# Lion1.net
KiCad netlist of a schematic drawn in EAGLE
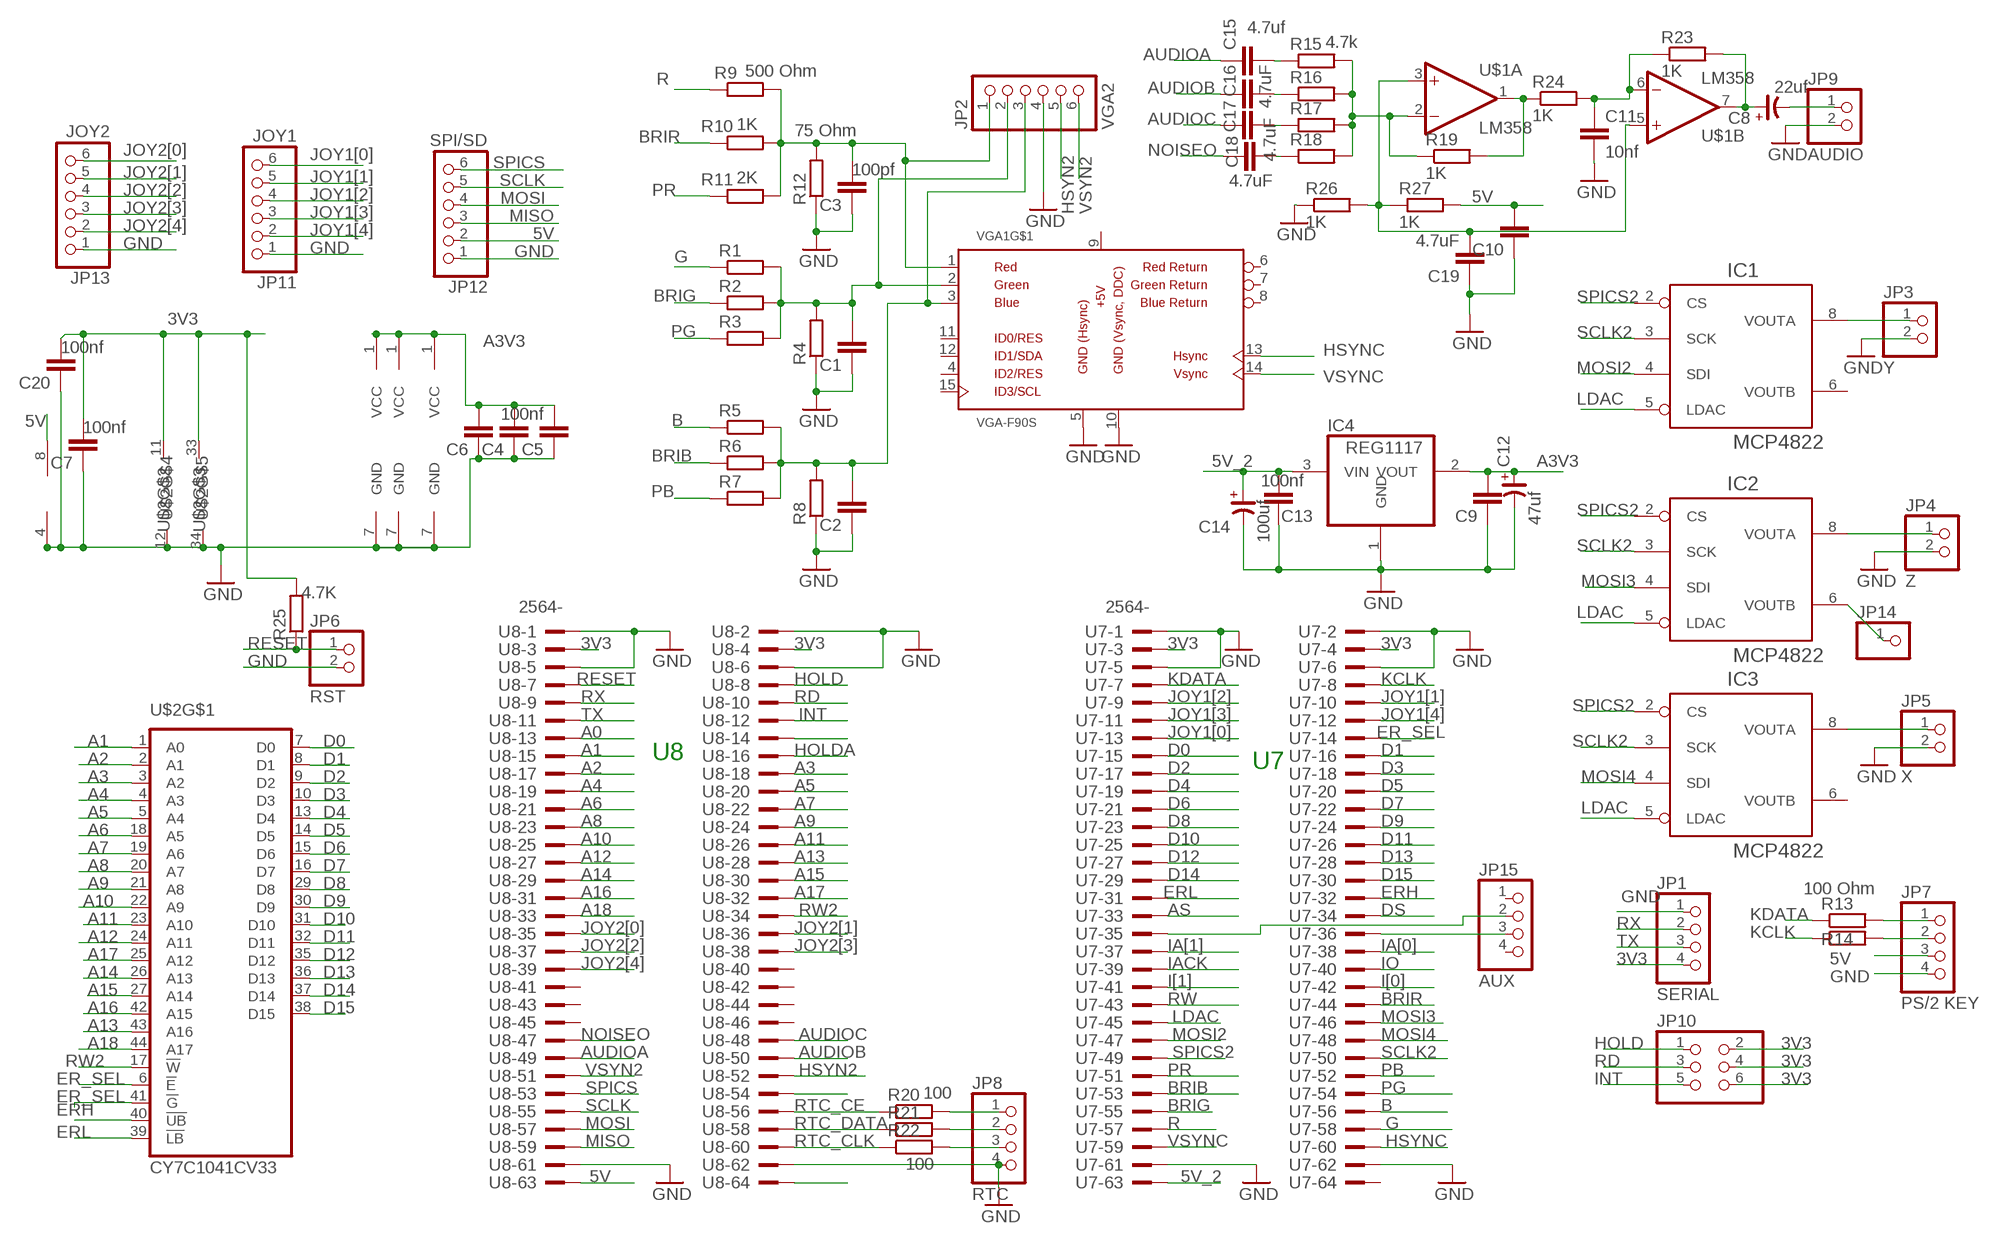
[diagram p0: schematic, sheet 1]

(export (version "E")
  (design (tool "Eeschema 10.0.6"))
  (components
    (comp (ref "C1")
      (value "C-EU050-025X075")
      (footprint "eagle-import:C050-025X075")
      (libsource (lib "eagle-import") (part "C-EU050-025X075"))
    )
    (comp (ref "C2")
      (value "C-EU050-025X075")
      (footprint "eagle-import:C050-025X075")
      (libsource (lib "eagle-import") (part "C-EU050-025X075"))
    )
    (comp (ref "C3")
      (value "100pf")
      (footprint "eagle-import:C050-025X075")
      (libsource (lib "eagle-import") (part "C-EU050-025X075"))
    )
    (comp (ref "C4")
      (value "C-EU050-025X075")
      (footprint "eagle-import:C050-025X075")
      (libsource (lib "eagle-import") (part "C-EU050-025X075"))
    )
    (comp (ref "C5")
      (value "100nf")
      (footprint "eagle-import:C050-025X075")
      (libsource (lib "eagle-import") (part "C-EU050-025X075"))
    )
    (comp (ref "C6")
      (value "C-EU050-025X075")
      (footprint "eagle-import:C050-025X075")
      (libsource (lib "eagle-import") (part "C-EU050-025X075"))
    )
    (comp (ref "C7")
      (value "100nf")
      (footprint "eagle-import:C0805")
      (libsource (lib "eagle-import") (part "C-EUC0805"))
    )
    (comp (ref "C8")
      (value "22uf")
      (footprint "eagle-import:CE-025X060")
      (libsource (lib "eagle-import") (part "CP_E-025X060"))
    )
    (comp (ref "C9")
      (value "C-EU050-025X075")
      (footprint "eagle-import:C050-025X075")
      (libsource (lib "eagle-import") (part "C-EU050-025X075"))
    )
    (comp (ref "C10")
      (value "C-EU050-025X075")
      (footprint "eagle-import:C050-025X075")
      (libsource (lib "eagle-import") (part "C-EU050-025X075"))
    )
    (comp (ref "C11")
      (value "10nf")
      (footprint "eagle-import:C050-025X075")
      (libsource (lib "eagle-import") (part "C-EU050-025X075"))
    )
    (comp (ref "C12")
      (value "47uf")
      (footprint "eagle-import:CE-025X060")
      (libsource (lib "eagle-import") (part "CP_E-025X060"))
    )
    (comp (ref "C13")
      (value "100nf")
      (footprint "eagle-import:C050-025X075")
      (libsource (lib "eagle-import") (part "C-EU050-025X075"))
    )
    (comp (ref "C14")
      (value "100uf")
      (footprint "eagle-import:CE-025X060")
      (libsource (lib "eagle-import") (part "CP_E-025X060"))
    )
    (comp (ref "C15")
      (value "4.7uf")
      (footprint "eagle-import:C050-025X075")
      (libsource (lib "eagle-import") (part "C-EU050-025X075"))
    )
    (comp (ref "C16")
      (value "4.7uF")
      (footprint "eagle-import:C050-025X075")
      (libsource (lib "eagle-import") (part "C-EU050-025X075"))
    )
    (comp (ref "C17")
      (value "4.7uF")
      (footprint "eagle-import:C050-025X075")
      (libsource (lib "eagle-import") (part "C-EU050-025X075"))
    )
    (comp (ref "C18")
      (value "4.7uF")
      (footprint "eagle-import:C050-025X075")
      (libsource (lib "eagle-import") (part "C-EU050-025X075"))
    )
    (comp (ref "C19")
      (value "4.7uF")
      (footprint "eagle-import:C050-025X075")
      (libsource (lib "eagle-import") (part "C-EU050-025X075"))
    )
    (comp (ref "C20")
      (value "100nf")
      (footprint "eagle-import:C0805")
      (libsource (lib "eagle-import") (part "C-EUC0805"))
    )
    (comp (ref "IC1")
      (value "MCP4822")
      (footprint "eagle-import:DIL08")
      (libsource (lib "eagle-import") (part "MCP42E-P"))
    )
    (comp (ref "IC2")
      (value "MCP4822")
      (footprint "eagle-import:DIL08")
      (libsource (lib "eagle-import") (part "MCP42E-P"))
    )
    (comp (ref "IC3")
      (value "MCP4822")
      (footprint "eagle-import:DIL08")
      (libsource (lib "eagle-import") (part "MCP42E-P"))
    )
    (comp (ref "IC4")
      (value "REG1117")
      (footprint "eagle-import:SOT223")
      (libsource (lib "eagle-import") (part "REG1117"))
    )
    (comp (ref "JP1")
      (value "SERIAL")
      (footprint "eagle-import:1X04")
      (libsource (lib "eagle-import") (part "PINHD-1X4"))
    )
    (comp (ref "JP2")
      (value "VGA2")
      (footprint "eagle-import:1X06")
      (libsource (lib "eagle-import") (part "PINHD-1X6"))
    )
    (comp (ref "JP3")
      (value "Y")
      (footprint "eagle-import:1X02")
      (libsource (lib "eagle-import") (part "PINHD-1X2"))
    )
    (comp (ref "JP4")
      (value "Z")
      (footprint "eagle-import:1X02")
      (libsource (lib "eagle-import") (part "PINHD-1X2"))
    )
    (comp (ref "JP5")
      (value "X")
      (footprint "eagle-import:1X02")
      (libsource (lib "eagle-import") (part "PINHD-1X2"))
    )
    (comp (ref "JP6")
      (value "RST")
      (footprint "eagle-import:1X02")
      (libsource (lib "eagle-import") (part "PINHD-1X2"))
    )
    (comp (ref "JP7")
      (value "PS/2 KEY")
      (footprint "eagle-import:1X04")
      (libsource (lib "eagle-import") (part "PINHD-1X4"))
    )
    (comp (ref "JP8")
      (value "RTC")
      (footprint "eagle-import:1X04")
      (libsource (lib "eagle-import") (part "PINHD-1X4"))
    )
    (comp (ref "JP9")
      (value "AUDIO")
      (footprint "eagle-import:1X02")
      (libsource (lib "eagle-import") (part "PINHD-1X2"))
    )
    (comp (ref "JP10")
      (value "PINHD-2X3")
      (footprint "eagle-import:2X03")
      (libsource (lib "eagle-import") (part "PINHD-2X3"))
    )
    (comp (ref "JP11")
      (value "JOY1")
      (footprint "eagle-import:1X06")
      (libsource (lib "eagle-import") (part "PINHD-1X6"))
    )
    (comp (ref "JP12")
      (value "SPI/SD")
      (footprint "eagle-import:1X06")
      (libsource (lib "eagle-import") (part "PINHD-1X6"))
    )
    (comp (ref "JP13")
      (value "JOY2")
      (footprint "eagle-import:1X06")
      (libsource (lib "eagle-import") (part "PINHD-1X6"))
    )
    (comp (ref "JP14")
      (value "PINHD-1X1")
      (footprint "eagle-import:1X01")
      (libsource (lib "eagle-import") (part "PINHD-1X1"))
    )
    (comp (ref "JP15")
      (value "AUX")
      (footprint "eagle-import:1X04")
      (libsource (lib "eagle-import") (part "PINHD-1X4"))
    )
    (comp (ref "R1")
      (value "R-EU_0204/7")
      (footprint "eagle-import:0204_7")
      (libsource (lib "eagle-import") (part "rcl_R-EU_0204/7"))
    )
    (comp (ref "R2")
      (value "R-EU_0204/7")
      (footprint "eagle-import:0204_7")
      (libsource (lib "eagle-import") (part "rcl_R-EU_0204/7"))
    )
    (comp (ref "R3")
      (value "R-EU_0204/7")
      (footprint "eagle-import:0204_7")
      (libsource (lib "eagle-import") (part "rcl_R-EU_0204/7"))
    )
    (comp (ref "R4")
      (value "R-EU_0204/7")
      (footprint "eagle-import:0204_7")
      (libsource (lib "eagle-import") (part "rcl_R-EU_0204/7"))
    )
    (comp (ref "R5")
      (value "R-EU_0204/7")
      (footprint "eagle-import:0204_7")
      (libsource (lib "eagle-import") (part "rcl_R-EU_0204/7"))
    )
    (comp (ref "R6")
      (value "R-EU_0204/7")
      (footprint "eagle-import:0204_7")
      (libsource (lib "eagle-import") (part "rcl_R-EU_0204/7"))
    )
    (comp (ref "R7")
      (value "R-EU_0204/7")
      (footprint "eagle-import:0204_7")
      (libsource (lib "eagle-import") (part "rcl_R-EU_0204/7"))
    )
    (comp (ref "R8")
      (value "R-EU_0204/7")
      (footprint "eagle-import:0204_7")
      (libsource (lib "eagle-import") (part "rcl_R-EU_0204/7"))
    )
    (comp (ref "R9")
      (value "500 Ohm")
      (footprint "eagle-import:0204_7")
      (libsource (lib "eagle-import") (part "rcl_R-EU_0204/7"))
    )
    (comp (ref "R10")
      (value "1K")
      (footprint "eagle-import:0204_7")
      (libsource (lib "eagle-import") (part "rcl_R-EU_0204/7"))
    )
    (comp (ref "R11")
      (value "2K")
      (footprint "eagle-import:0204_7")
      (libsource (lib "eagle-import") (part "rcl_R-EU_0204/7"))
    )
    (comp (ref "R12")
      (value "75 Ohm")
      (footprint "eagle-import:0204_7")
      (libsource (lib "eagle-import") (part "rcl_R-EU_0204/7"))
    )
    (comp (ref "R13")
      (value "100 Ohm")
      (footprint "eagle-import:0204_7")
      (libsource (lib "eagle-import") (part "R-EU_0204/7"))
    )
    (comp (ref "R14")
      (value "R-EU_0204/7")
      (footprint "eagle-import:0204_7")
      (libsource (lib "eagle-import") (part "R-EU_0204/7"))
    )
    (comp (ref "R15")
      (value "4.7k")
      (footprint "eagle-import:0204V")
      (libsource (lib "eagle-import") (part "R-EU_0204/2V"))
    )
    (comp (ref "R16")
      (value "R-EU_0204/2V")
      (footprint "eagle-import:0204V")
      (libsource (lib "eagle-import") (part "R-EU_0204/2V"))
    )
    (comp (ref "R17")
      (value "R-EU_0204/2V")
      (footprint "eagle-import:0204V")
      (libsource (lib "eagle-import") (part "R-EU_0204/2V"))
    )
    (comp (ref "R18")
      (value "R-EU_0204/2V")
      (footprint "eagle-import:0204V")
      (libsource (lib "eagle-import") (part "R-EU_0204/2V"))
    )
    (comp (ref "R19")
      (value "1K")
      (footprint "eagle-import:0204_7")
      (libsource (lib "eagle-import") (part "R-EU_0204/7"))
    )
    (comp (ref "R20")
      (value "100")
      (footprint "eagle-import:0204_7")
      (libsource (lib "eagle-import") (part "R-EU_0204/7"))
    )
    (comp (ref "R21")
      (value "100")
      (footprint "eagle-import:0204_7")
      (libsource (lib "eagle-import") (part "R-EU_0204/7"))
    )
    (comp (ref "R22")
      (value "R-EU_0204/7")
      (footprint "eagle-import:0204_7")
      (libsource (lib "eagle-import") (part "R-EU_0204/7"))
    )
    (comp (ref "R23")
      (value "1K")
      (footprint "eagle-import:0204_7")
      (libsource (lib "eagle-import") (part "R-EU_0204/7"))
    )
    (comp (ref "R24")
      (value "1K")
      (footprint "eagle-import:0204_7")
      (libsource (lib "eagle-import") (part "R-EU_0204/7"))
    )
    (comp (ref "R25")
      (value "4.7K")
      (footprint "eagle-import:0204_5")
      (libsource (lib "eagle-import") (part "rcl_R-EU_0204/5"))
    )
    (comp (ref "R26")
      (value "1K")
      (footprint "eagle-import:0204_7")
      (libsource (lib "eagle-import") (part "R-EU_0204/7"))
    )
    (comp (ref "R27")
      (value "1K")
      (footprint "eagle-import:0204_7")
      (libsource (lib "eagle-import") (part "R-EU_0204/7"))
    )
    (comp (ref "U$1")
      (value "LM358")
      (footprint "eagle-import:DIL8")
      (libsource (lib "eagle-import") (part "LM358"))
    )
    (comp (ref "U$2")
      (value "CY7C1041CV33")
      (footprint "eagle-import:TSOP44-II")
      (libsource (lib "eagle-import") (part "CY7C1041CV33"))
    )
    (comp (ref "U7")
      (value "2564-")
      (footprint "eagle-import:PAK100_2500-64")
      (libsource (lib "eagle-import") (part "2564-"))
    )
    (comp (ref "U8")
      (value "2564-")
      (footprint "eagle-import:PAK100_2500-64")
      (libsource (lib "eagle-import") (part "2564-"))
    )
    (comp (ref "VGA1")
      (value "VGA-F90S")
      (footprint "eagle-import:DB-15-F90+SHIELD-SMALL_PADS")
      (libsource (lib "eagle-import") (part "VGA-F90S"))
    )
  )
  (nets
    (net (code "1") (name "/+5V") (class "Default")
      (node (ref "VGA1") (pin "9") (pinfunction "+5V_9") (pintype "power_in"))
    )
    (net (code "2") (name "/3V3") (class "Default")
      (node (ref "C20") (pin "2") (pinfunction "2_2") (pintype "passive"))
      (node (ref "C7") (pin "2") (pinfunction "2_2") (pintype "passive"))
      (node (ref "JP1") (pin "4") (pinfunction "4_4") (pintype "passive"))
      (node (ref "JP10") (pin "2") (pinfunction "2_2") (pintype "passive"))
      (node (ref "JP10") (pin "4") (pinfunction "4_4") (pintype "passive"))
      (node (ref "JP10") (pin "6") (pinfunction "6_6") (pintype "passive"))
      (node (ref "R25") (pin "2") (pinfunction "2_2") (pintype "passive"))
      (node (ref "U$2") (pin "11") (pinfunction "VCC_11") (pintype "power_in"))
      (node (ref "U$2") (pin "33") (pinfunction "VCC_33") (pintype "power_in"))
      (node (ref "U7") (pin "3") (pinfunction "KL_3") (pintype "passive"))
      (node (ref "U7") (pin "4") (pinfunction "KL_4") (pintype "passive"))
      (node (ref "U8") (pin "3") (pinfunction "KL_3") (pintype "passive"))
      (node (ref "U8") (pin "4") (pinfunction "KL_4") (pintype "passive"))
    )
    (net (code "3") (name "/5V") (class "Default")
      (node (ref "C10") (pin "2") (pinfunction "2_2") (pintype "passive"))
      (node (ref "JP12") (pin "2") (pinfunction "2_2") (pintype "passive"))
      (node (ref "JP7") (pin "3") (pinfunction "3_3") (pintype "passive"))
      (node (ref "R27") (pin "2") (pinfunction "2_2") (pintype "passive"))
      (node (ref "U$1") (pin "8") (pinfunction "V+_8") (pintype "power_in"))
      (node (ref "U8") (pin "63") (pinfunction "KL_63") (pintype "passive"))
    )
    (net (code "4") (name "/5V_2") (class "Default")
      (node (ref "C13") (pin "2") (pinfunction "2_2") (pintype "passive"))
      (node (ref "C14") (pin "+") (pinfunction "+_+") (pintype "passive"))
      (node (ref "IC4") (pin "3") (pinfunction "VIN_3") (pintype "input"))
      (node (ref "U7") (pin "63") (pinfunction "KL_63") (pintype "passive"))
    )
    (net (code "5") (name "/A0") (class "Default")
      (node (ref "U8") (pin "13") (pinfunction "KL_13") (pintype "passive"))
    )
    (net (code "6") (name "/A1") (class "Default")
      (node (ref "U$2") (pin "1") (pinfunction "A0_1") (pintype "input"))
      (node (ref "U8") (pin "15") (pinfunction "KL_15") (pintype "passive"))
    )
    (net (code "7") (name "/A2") (class "Default")
      (node (ref "U$2") (pin "2") (pinfunction "A1_2") (pintype "input"))
      (node (ref "U8") (pin "17") (pinfunction "KL_17") (pintype "passive"))
    )
    (net (code "8") (name "/A3") (class "Default")
      (node (ref "U$2") (pin "3") (pinfunction "A2_3") (pintype "input"))
      (node (ref "U8") (pin "18") (pinfunction "KL_18") (pintype "passive"))
    )
    (net (code "9") (name "/A3V3") (class "Default")
      (node (ref "C12") (pin "+") (pinfunction "+_+") (pintype "passive"))
      (node (ref "C4") (pin "2") (pinfunction "2_2") (pintype "passive"))
      (node (ref "C5") (pin "2") (pinfunction "2_2") (pintype "passive"))
      (node (ref "C6") (pin "2") (pinfunction "2_2") (pintype "passive"))
      (node (ref "C9") (pin "2") (pinfunction "2_2") (pintype "passive"))
      (node (ref "IC1") (pin "1") (pinfunction "VCC_1") (pintype "power_in"))
      (node (ref "IC2") (pin "1") (pinfunction "VCC_1") (pintype "power_in"))
      (node (ref "IC3") (pin "1") (pinfunction "VCC_1") (pintype "power_in"))
      (node (ref "IC4") (pin "2") (pinfunction "VOUT_2") (pintype "output"))
    )
    (net (code "10") (name "/A4") (class "Default")
      (node (ref "U$2") (pin "4") (pinfunction "A3_4") (pintype "input"))
      (node (ref "U8") (pin "19") (pinfunction "KL_19") (pintype "passive"))
    )
    (net (code "11") (name "/A5") (class "Default")
      (node (ref "U$2") (pin "5") (pinfunction "A4_5") (pintype "input"))
      (node (ref "U8") (pin "20") (pinfunction "KL_20") (pintype "passive"))
    )
    (net (code "12") (name "/A6") (class "Default")
      (node (ref "U$2") (pin "18") (pinfunction "A5_18") (pintype "input"))
      (node (ref "U8") (pin "21") (pinfunction "KL_21") (pintype "passive"))
    )
    (net (code "13") (name "/A7") (class "Default")
      (node (ref "U$2") (pin "19") (pinfunction "A6_19") (pintype "input"))
      (node (ref "U8") (pin "22") (pinfunction "KL_22") (pintype "passive"))
    )
    (net (code "14") (name "/A8") (class "Default")
      (node (ref "U$2") (pin "20") (pinfunction "A7_20") (pintype "input"))
      (node (ref "U8") (pin "23") (pinfunction "KL_23") (pintype "passive"))
    )
    (net (code "15") (name "/A9") (class "Default")
      (node (ref "U$2") (pin "21") (pinfunction "A8_21") (pintype "input"))
      (node (ref "U8") (pin "24") (pinfunction "KL_24") (pintype "passive"))
    )
    (net (code "16") (name "/A10") (class "Default")
      (node (ref "U$2") (pin "22") (pinfunction "A9_22") (pintype "input"))
      (node (ref "U8") (pin "25") (pinfunction "KL_25") (pintype "passive"))
    )
    (net (code "17") (name "/A11") (class "Default")
      (node (ref "U$2") (pin "23") (pinfunction "A10_23") (pintype "input"))
      (node (ref "U8") (pin "26") (pinfunction "KL_26") (pintype "passive"))
    )
    (net (code "18") (name "/A12") (class "Default")
      (node (ref "U$2") (pin "24") (pinfunction "A11_24") (pintype "input"))
      (node (ref "U8") (pin "27") (pinfunction "KL_27") (pintype "passive"))
    )
    (net (code "19") (name "/A13") (class "Default")
      (node (ref "U$2") (pin "43") (pinfunction "A16_43") (pintype "input"))
      (node (ref "U8") (pin "28") (pinfunction "KL_28") (pintype "passive"))
    )
    (net (code "20") (name "/A14") (class "Default")
      (node (ref "U$2") (pin "26") (pinfunction "A13_26") (pintype "input"))
      (node (ref "U8") (pin "29") (pinfunction "KL_29") (pintype "passive"))
    )
    (net (code "21") (name "/A15") (class "Default")
      (node (ref "U$2") (pin "27") (pinfunction "A14_27") (pintype "input"))
      (node (ref "U8") (pin "30") (pinfunction "KL_30") (pintype "passive"))
    )
    (net (code "22") (name "/A16") (class "Default")
      (node (ref "U$2") (pin "42") (pinfunction "A15_42") (pintype "input"))
      (node (ref "U8") (pin "31") (pinfunction "KL_31") (pintype "passive"))
    )
    (net (code "23") (name "/A17") (class "Default")
      (node (ref "U$2") (pin "25") (pinfunction "A12_25") (pintype "input"))
      (node (ref "U8") (pin "32") (pinfunction "KL_32") (pintype "passive"))
    )
    (net (code "24") (name "/A18") (class "Default")
      (node (ref "U$2") (pin "44") (pinfunction "A17_44") (pintype "input"))
      (node (ref "U8") (pin "33") (pinfunction "KL_33") (pintype "passive"))
    )
    (net (code "25") (name "/AS") (class "Default")
      (node (ref "U7") (pin "33") (pinfunction "KL_33") (pintype "passive"))
    )
    (net (code "26") (name "/AUDIOA") (class "Default")
      (node (ref "C15") (pin "1") (pinfunction "1_1") (pintype "passive"))
      (node (ref "U8") (pin "49") (pinfunction "KL_49") (pintype "passive"))
    )
    (net (code "27") (name "/AUDIOB") (class "Default")
      (node (ref "C16") (pin "1") (pinfunction "1_1") (pintype "passive"))
      (node (ref "U8") (pin "50") (pinfunction "KL_50") (pintype "passive"))
    )
    (net (code "28") (name "/AUDIOC") (class "Default")
      (node (ref "C17") (pin "1") (pinfunction "1_1") (pintype "passive"))
      (node (ref "U8") (pin "48") (pinfunction "KL_48") (pintype "passive"))
    )
    (net (code "29") (name "/B") (class "Default")
      (node (ref "R5") (pin "1") (pinfunction "1_1") (pintype "passive"))
      (node (ref "U7") (pin "56") (pinfunction "KL_56") (pintype "passive"))
    )
    (net (code "30") (name "/BRIB") (class "Default")
      (node (ref "R6") (pin "1") (pinfunction "1_1") (pintype "passive"))
      (node (ref "U7") (pin "53") (pinfunction "KL_53") (pintype "passive"))
    )
    (net (code "31") (name "/BRIG") (class "Default")
      (node (ref "R2") (pin "1") (pinfunction "1_1") (pintype "passive"))
      (node (ref "U7") (pin "55") (pinfunction "KL_55") (pintype "passive"))
    )
    (net (code "32") (name "/BRIR") (class "Default")
      (node (ref "R10") (pin "1") (pinfunction "1_1") (pintype "passive"))
      (node (ref "U7") (pin "44") (pinfunction "KL_44") (pintype "passive"))
    )
    (net (code "33") (name "/D0") (class "Default")
      (node (ref "U$2") (pin "7") (pinfunction "D0_7") (pintype "tri_state"))
      (node (ref "U7") (pin "15") (pinfunction "KL_15") (pintype "passive"))
    )
    (net (code "34") (name "/D1") (class "Default")
      (node (ref "U$2") (pin "8") (pinfunction "D1_8") (pintype "tri_state"))
      (node (ref "U7") (pin "16") (pinfunction "KL_16") (pintype "passive"))
    )
    (net (code "35") (name "/D2") (class "Default")
      (node (ref "U$2") (pin "9") (pinfunction "D2_9") (pintype "tri_state"))
      (node (ref "U7") (pin "17") (pinfunction "KL_17") (pintype "passive"))
    )
    (net (code "36") (name "/D3") (class "Default")
      (node (ref "U$2") (pin "10") (pinfunction "D3_10") (pintype "tri_state"))
      (node (ref "U7") (pin "18") (pinfunction "KL_18") (pintype "passive"))
    )
    (net (code "37") (name "/D4") (class "Default")
      (node (ref "U$2") (pin "13") (pinfunction "D4_13") (pintype "tri_state"))
      (node (ref "U7") (pin "19") (pinfunction "KL_19") (pintype "passive"))
    )
    (net (code "38") (name "/D5") (class "Default")
      (node (ref "U$2") (pin "14") (pinfunction "D5_14") (pintype "tri_state"))
      (node (ref "U7") (pin "20") (pinfunction "KL_20") (pintype "passive"))
    )
    (net (code "39") (name "/D6") (class "Default")
      (node (ref "U$2") (pin "15") (pinfunction "D6_15") (pintype "tri_state"))
      (node (ref "U7") (pin "21") (pinfunction "KL_21") (pintype "passive"))
    )
    (net (code "40") (name "/D7") (class "Default")
      (node (ref "U$2") (pin "16") (pinfunction "D7_16") (pintype "tri_state"))
      (node (ref "U7") (pin "22") (pinfunction "KL_22") (pintype "passive"))
    )
    (net (code "41") (name "/D8") (class "Default")
      (node (ref "U$2") (pin "29") (pinfunction "D8_29") (pintype "tri_state"))
      (node (ref "U7") (pin "23") (pinfunction "KL_23") (pintype "passive"))
    )
    (net (code "42") (name "/D9") (class "Default")
      (node (ref "U$2") (pin "30") (pinfunction "D9_30") (pintype "tri_state"))
      (node (ref "U7") (pin "24") (pinfunction "KL_24") (pintype "passive"))
    )
    (net (code "43") (name "/D10") (class "Default")
      (node (ref "U$2") (pin "31") (pinfunction "D10_31") (pintype "tri_state"))
      (node (ref "U7") (pin "25") (pinfunction "KL_25") (pintype "passive"))
    )
    (net (code "44") (name "/D11") (class "Default")
      (node (ref "U$2") (pin "32") (pinfunction "D11_32") (pintype "tri_state"))
      (node (ref "U7") (pin "26") (pinfunction "KL_26") (pintype "passive"))
    )
    (net (code "45") (name "/D12") (class "Default")
      (node (ref "U$2") (pin "35") (pinfunction "D12_35") (pintype "tri_state"))
      (node (ref "U7") (pin "27") (pinfunction "KL_27") (pintype "passive"))
    )
    (net (code "46") (name "/D13") (class "Default")
      (node (ref "U$2") (pin "36") (pinfunction "D13_36") (pintype "tri_state"))
      (node (ref "U7") (pin "28") (pinfunction "KL_28") (pintype "passive"))
    )
    (net (code "47") (name "/D14") (class "Default")
      (node (ref "U$2") (pin "37") (pinfunction "D14_37") (pintype "tri_state"))
      (node (ref "U7") (pin "29") (pinfunction "KL_29") (pintype "passive"))
    )
    (net (code "48") (name "/D15") (class "Default")
      (node (ref "U$2") (pin "38") (pinfunction "D15_38") (pintype "tri_state"))
      (node (ref "U7") (pin "30") (pinfunction "KL_30") (pintype "passive"))
    )
    (net (code "49") (name "/DS") (class "Default")
      (node (ref "U7") (pin "34") (pinfunction "KL_34") (pintype "passive"))
    )
    (net (code "50") (name "/ERH") (class "Default")
      (node (ref "U$2") (pin "40") (pinfunction "~{UB}_40") (pintype "input"))
      (node (ref "U7") (pin "32") (pinfunction "KL_32") (pintype "passive"))
    )
    (net (code "51") (name "/ERL") (class "Default")
      (node (ref "U$2") (pin "39") (pinfunction "~{LB}_39") (pintype "input"))
      (node (ref "U7") (pin "31") (pinfunction "KL_31") (pintype "passive"))
    )
    (net (code "52") (name "/ER_SEL") (class "Default")
      (node (ref "U$2") (pin "41") (pinfunction "~{G}_41") (pintype "input"))
      (node (ref "U$2") (pin "6") (pinfunction "~{E}_6") (pintype "input"))
      (node (ref "U7") (pin "14") (pinfunction "KL_14") (pintype "passive"))
    )
    (net (code "53") (name "/G") (class "Default")
      (node (ref "R1") (pin "1") (pinfunction "1_1") (pintype "passive"))
      (node (ref "U7") (pin "58") (pinfunction "KL_58") (pintype "passive"))
    )
    (net (code "54") (name "/HOLD") (class "Default")
      (node (ref "JP10") (pin "1") (pinfunction "1_1") (pintype "passive"))
      (node (ref "U8") (pin "8") (pinfunction "KL_8") (pintype "passive"))
    )
    (net (code "55") (name "/HOLDA") (class "Default")
      (node (ref "U8") (pin "16") (pinfunction "KL_16") (pintype "passive"))
    )
    (net (code "56") (name "/HSYN2") (class "Default")
      (node (ref "JP2") (pin "5") (pinfunction "5_5") (pintype "passive"))
      (node (ref "U8") (pin "52") (pinfunction "KL_52") (pintype "passive"))
    )
    (net (code "57") (name "/HSYNC") (class "Default")
      (node (ref "U7") (pin "60") (pinfunction "KL_60") (pintype "passive"))
      (node (ref "VGA1") (pin "13") (pinfunction "VGA-HSYNC_13") (pintype "bidirectional"))
    )
    (net (code "58") (name "/IACK") (class "Default")
      (node (ref "U7") (pin "39") (pinfunction "KL_39") (pintype "passive"))
    )
    (net (code "59") (name "/IA[0]") (class "Default")
      (node (ref "U7") (pin "38") (pinfunction "KL_38") (pintype "passive"))
    )
    (net (code "60") (name "/IA[1]") (class "Default")
      (node (ref "U7") (pin "37") (pinfunction "KL_37") (pintype "passive"))
    )
    (net (code "61") (name "/INT") (class "Default")
      (node (ref "JP10") (pin "5") (pinfunction "5_5") (pintype "passive"))
      (node (ref "U8") (pin "12") (pinfunction "KL_12") (pintype "passive"))
    )
    (net (code "62") (name "/IO") (class "Default")
      (node (ref "U7") (pin "40") (pinfunction "KL_40") (pintype "passive"))
    )
    (net (code "63") (name "/I[0]") (class "Default")
      (node (ref "U7") (pin "42") (pinfunction "KL_42") (pintype "passive"))
    )
    (net (code "64") (name "/I[1]") (class "Default")
      (node (ref "U7") (pin "41") (pinfunction "KL_41") (pintype "passive"))
    )
    (net (code "65") (name "/JOY1[0]") (class "Default")
      (node (ref "JP11") (pin "6") (pinfunction "6_6") (pintype "passive"))
      (node (ref "U7") (pin "13") (pinfunction "KL_13") (pintype "passive"))
    )
    (net (code "66") (name "/JOY1[1]") (class "Default")
      (node (ref "JP11") (pin "5") (pinfunction "5_5") (pintype "passive"))
      (node (ref "U7") (pin "10") (pinfunction "KL_10") (pintype "passive"))
    )
    (net (code "67") (name "/JOY1[2]") (class "Default")
      (node (ref "JP11") (pin "4") (pinfunction "4_4") (pintype "passive"))
      (node (ref "U7") (pin "9") (pinfunction "KL_9") (pintype "passive"))
    )
    (net (code "68") (name "/JOY1[3]") (class "Default")
      (node (ref "JP11") (pin "3") (pinfunction "3_3") (pintype "passive"))
      (node (ref "U7") (pin "11") (pinfunction "KL_11") (pintype "passive"))
    )
    (net (code "69") (name "/JOY1[4]") (class "Default")
      (node (ref "JP11") (pin "2") (pinfunction "2_2") (pintype "passive"))
      (node (ref "U7") (pin "12") (pinfunction "KL_12") (pintype "passive"))
    )
    (net (code "70") (name "/JOY2[0]") (class "Default")
      (node (ref "JP13") (pin "6") (pinfunction "6_6") (pintype "passive"))
      (node (ref "U8") (pin "35") (pinfunction "KL_35") (pintype "passive"))
    )
    (net (code "71") (name "/JOY2[1]") (class "Default")
      (node (ref "JP13") (pin "5") (pinfunction "5_5") (pintype "passive"))
      (node (ref "U8") (pin "36") (pinfunction "KL_36") (pintype "passive"))
    )
    (net (code "72") (name "/JOY2[2]") (class "Default")
      (node (ref "JP13") (pin "4") (pinfunction "4_4") (pintype "passive"))
      (node (ref "U8") (pin "37") (pinfunction "KL_37") (pintype "passive"))
    )
    (net (code "73") (name "/JOY2[3]") (class "Default")
      (node (ref "JP13") (pin "3") (pinfunction "3_3") (pintype "passive"))
      (node (ref "U8") (pin "38") (pinfunction "KL_38") (pintype "passive"))
    )
    (net (code "74") (name "/JOY2[4]") (class "Default")
      (node (ref "JP13") (pin "2") (pinfunction "2_2") (pintype "passive"))
      (node (ref "U8") (pin "39") (pinfunction "KL_39") (pintype "passive"))
    )
    (net (code "75") (name "/KCLK") (class "Default")
      (node (ref "R14") (pin "1") (pinfunction "1_1") (pintype "passive"))
      (node (ref "U7") (pin "8") (pinfunction "KL_8") (pintype "passive"))
    )
    (net (code "76") (name "/KDATA") (class "Default")
      (node (ref "R13") (pin "1") (pinfunction "1_1") (pintype "passive"))
      (node (ref "U7") (pin "7") (pinfunction "KL_7") (pintype "passive"))
    )
    (net (code "77") (name "/LDAC") (class "Default")
      (node (ref "IC1") (pin "5") (pinfunction "LDAC_5") (pintype "input"))
      (node (ref "IC2") (pin "5") (pinfunction "LDAC_5") (pintype "input"))
      (node (ref "IC3") (pin "5") (pinfunction "LDAC_5") (pintype "input"))
      (node (ref "U7") (pin "45") (pinfunction "KL_45") (pintype "passive"))
    )
    (net (code "78") (name "/MISO") (class "Default")
      (node (ref "JP12") (pin "3") (pinfunction "3_3") (pintype "passive"))
      (node (ref "U8") (pin "59") (pinfunction "KL_59") (pintype "passive"))
    )
    (net (code "79") (name "/MOSI") (class "Default")
      (node (ref "JP12") (pin "4") (pinfunction "4_4") (pintype "passive"))
      (node (ref "U8") (pin "57") (pinfunction "KL_57") (pintype "passive"))
    )
    (net (code "80") (name "/MOSI2") (class "Default")
      (node (ref "IC1") (pin "4") (pinfunction "SDI_4") (pintype "input"))
      (node (ref "U7") (pin "47") (pinfunction "KL_47") (pintype "passive"))
    )
    (net (code "81") (name "/MOSI3") (class "Default")
      (node (ref "IC2") (pin "4") (pinfunction "SDI_4") (pintype "input"))
      (node (ref "U7") (pin "46") (pinfunction "KL_46") (pintype "passive"))
    )
    (net (code "82") (name "/MOSI4") (class "Default")
      (node (ref "IC3") (pin "4") (pinfunction "SDI_4") (pintype "input"))
      (node (ref "U7") (pin "48") (pinfunction "KL_48") (pintype "passive"))
    )
    (net (code "83") (name "/NOISEO") (class "Default")
      (node (ref "C18") (pin "1") (pinfunction "1_1") (pintype "passive"))
      (node (ref "U8") (pin "47") (pinfunction "KL_47") (pintype "passive"))
    )
    (net (code "84") (name "/PB") (class "Default")
      (node (ref "R7") (pin "1") (pinfunction "1_1") (pintype "passive"))
      (node (ref "U7") (pin "52") (pinfunction "KL_52") (pintype "passive"))
    )
    (net (code "85") (name "/PG") (class "Default")
      (node (ref "R3") (pin "1") (pinfunction "1_1") (pintype "passive"))
      (node (ref "U7") (pin "54") (pinfunction "KL_54") (pintype "passive"))
    )
    (net (code "86") (name "/PR") (class "Default")
      (node (ref "R11") (pin "1") (pinfunction "1_1") (pintype "passive"))
      (node (ref "U7") (pin "51") (pinfunction "KL_51") (pintype "passive"))
    )
    (net (code "87") (name "/R") (class "Default")
      (node (ref "R9") (pin "1") (pinfunction "1_1") (pintype "passive"))
      (node (ref "U7") (pin "57") (pinfunction "KL_57") (pintype "passive"))
    )
    (net (code "88") (name "/RD") (class "Default")
      (node (ref "JP10") (pin "3") (pinfunction "3_3") (pintype "passive"))
      (node (ref "U8") (pin "10") (pinfunction "KL_10") (pintype "passive"))
    )
    (net (code "89") (name "/RESET") (class "Default")
      (node (ref "JP6") (pin "1") (pinfunction "1_1") (pintype "passive"))
      (node (ref "R25") (pin "1") (pinfunction "1_1") (pintype "passive"))
      (node (ref "U8") (pin "7") (pinfunction "KL_7") (pintype "passive"))
    )
    (net (code "90") (name "/RTC_CE") (class "Default")
      (node (ref "R20") (pin "1") (pinfunction "1_1") (pintype "passive"))
      (node (ref "U8") (pin "56") (pinfunction "KL_56") (pintype "passive"))
    )
    (net (code "91") (name "/RTC_CLK") (class "Default")
      (node (ref "R22") (pin "1") (pinfunction "1_1") (pintype "passive"))
      (node (ref "U8") (pin "60") (pinfunction "KL_60") (pintype "passive"))
    )
    (net (code "92") (name "/RTC_DATA") (class "Default")
      (node (ref "R21") (pin "1") (pinfunction "1_1") (pintype "passive"))
      (node (ref "U8") (pin "58") (pinfunction "KL_58") (pintype "passive"))
    )
    (net (code "93") (name "/RW") (class "Default")
      (node (ref "U7") (pin "43") (pinfunction "KL_43") (pintype "passive"))
    )
    (net (code "94") (name "/RW2") (class "Default")
      (node (ref "U$2") (pin "17") (pinfunction "~{W}_17") (pintype "input"))
      (node (ref "U8") (pin "34") (pinfunction "KL_34") (pintype "passive"))
    )
    (net (code "95") (name "/RX") (class "Default")
      (node (ref "JP1") (pin "2") (pinfunction "2_2") (pintype "passive"))
      (node (ref "U8") (pin "9") (pinfunction "KL_9") (pintype "passive"))
    )
    (net (code "96") (name "/SCLK") (class "Default")
      (node (ref "JP12") (pin "5") (pinfunction "5_5") (pintype "passive"))
      (node (ref "U8") (pin "55") (pinfunction "KL_55") (pintype "passive"))
    )
    (net (code "97") (name "/SCLK2") (class "Default")
      (node (ref "IC1") (pin "3") (pinfunction "SCK_3") (pintype "input"))
      (node (ref "IC2") (pin "3") (pinfunction "SCK_3") (pintype "input"))
      (node (ref "IC3") (pin "3") (pinfunction "SCK_3") (pintype "input"))
      (node (ref "U7") (pin "50") (pinfunction "KL_50") (pintype "passive"))
    )
    (net (code "98") (name "/SPICS") (class "Default")
      (node (ref "JP12") (pin "6") (pinfunction "6_6") (pintype "passive"))
      (node (ref "U8") (pin "53") (pinfunction "KL_53") (pintype "passive"))
    )
    (net (code "99") (name "/SPICS2") (class "Default")
      (node (ref "IC1") (pin "2") (pinfunction "CS_2") (pintype "input"))
      (node (ref "IC2") (pin "2") (pinfunction "CS_2") (pintype "input"))
      (node (ref "IC3") (pin "2") (pinfunction "CS_2") (pintype "input"))
      (node (ref "U7") (pin "49") (pinfunction "KL_49") (pintype "passive"))
    )
    (net (code "100") (name "/TX") (class "Default")
      (node (ref "JP1") (pin "3") (pinfunction "3_3") (pintype "passive"))
      (node (ref "U8") (pin "11") (pinfunction "KL_11") (pintype "passive"))
    )
    (net (code "101") (name "/VSYN2") (class "Default")
      (node (ref "JP2") (pin "6") (pinfunction "6_6") (pintype "passive"))
      (node (ref "U8") (pin "51") (pinfunction "KL_51") (pintype "passive"))
    )
    (net (code "102") (name "/VSYNC") (class "Default")
      (node (ref "U7") (pin "59") (pinfunction "KL_59") (pintype "passive"))
      (node (ref "VGA1") (pin "14") (pinfunction "VGA-VSYNC_14") (pintype "bidirectional"))
    )
    (net (code "103") (name "GND") (class "Default")
      (node (ref "C1") (pin "1") (pinfunction "1_1") (pintype "passive"))
      (node (ref "C10") (pin "1") (pinfunction "1_1") (pintype "passive"))
      (node (ref "C11") (pin "2") (pinfunction "2_2") (pintype "passive"))
      (node (ref "C12") (pin "-") (pinfunction "-_-") (pintype "passive"))
      (node (ref "C13") (pin "1") (pinfunction "1_1") (pintype "passive"))
      (node (ref "C14") (pin "-") (pinfunction "-_-") (pintype "passive"))
      (node (ref "C19") (pin "1") (pinfunction "1_1") (pintype "passive"))
      (node (ref "C2") (pin "1") (pinfunction "1_1") (pintype "passive"))
      (node (ref "C20") (pin "1") (pinfunction "1_1") (pintype "passive"))
      (node (ref "C3") (pin "1") (pinfunction "1_1") (pintype "passive"))
      (node (ref "C4") (pin "1") (pinfunction "1_1") (pintype "passive"))
      (node (ref "C5") (pin "1") (pinfunction "1_1") (pintype "passive"))
      (node (ref "C6") (pin "1") (pinfunction "1_1") (pintype "passive"))
      (node (ref "C7") (pin "1") (pinfunction "1_1") (pintype "passive"))
      (node (ref "C9") (pin "1") (pinfunction "1_1") (pintype "passive"))
      (node (ref "IC1") (pin "7") (pinfunction "GND_7") (pintype "power_in"))
      (node (ref "IC2") (pin "7") (pinfunction "GND_7") (pintype "power_in"))
      (node (ref "IC3") (pin "7") (pinfunction "GND_7") (pintype "power_in"))
      (node (ref "IC4") (pin "1") (pinfunction "GND_1") (pintype "power_in"))
      (node (ref "JP1") (pin "1") (pinfunction "1_1") (pintype "passive"))
      (node (ref "JP11") (pin "1") (pinfunction "1_1") (pintype "passive"))
      (node (ref "JP12") (pin "1") (pinfunction "1_1") (pintype "passive"))
      (node (ref "JP13") (pin "1") (pinfunction "1_1") (pintype "passive"))
      (node (ref "JP2") (pin "4") (pinfunction "4_4") (pintype "passive"))
      (node (ref "JP3") (pin "2") (pinfunction "2_2") (pintype "passive"))
      (node (ref "JP4") (pin "2") (pinfunction "2_2") (pintype "passive"))
      (node (ref "JP5") (pin "2") (pinfunction "2_2") (pintype "passive"))
      (node (ref "JP6") (pin "2") (pinfunction "2_2") (pintype "passive"))
      (node (ref "JP7") (pin "4") (pinfunction "4_4") (pintype "passive"))
      (node (ref "JP8") (pin "4") (pinfunction "4_4") (pintype "passive"))
      (node (ref "JP9") (pin "2") (pinfunction "2_2") (pintype "passive"))
      (node (ref "R12") (pin "1") (pinfunction "1_1") (pintype "passive"))
      (node (ref "R26") (pin "1") (pinfunction "1_1") (pintype "passive"))
      (node (ref "R4") (pin "1") (pinfunction "1_1") (pintype "passive"))
      (node (ref "R8") (pin "1") (pinfunction "1_1") (pintype "passive"))
      (node (ref "U$1") (pin "4") (pinfunction "V-_4") (pintype "power_in"))
      (node (ref "U$2") (pin "12") (pinfunction "VSS_12") (pintype "power_in"))
      (node (ref "U$2") (pin "34") (pinfunction "VSS_34") (pintype "power_in"))
      (node (ref "U7") (pin "1") (pinfunction "KL_1") (pintype "passive"))
      (node (ref "U7") (pin "2") (pinfunction "KL_2") (pintype "passive"))
      (node (ref "U7") (pin "5") (pinfunction "KL_5") (pintype "passive"))
      (node (ref "U7") (pin "6") (pinfunction "KL_6") (pintype "passive"))
      (node (ref "U7") (pin "61") (pinfunction "KL_61") (pintype "passive"))
      (node (ref "U7") (pin "62") (pinfunction "KL_62") (pintype "passive"))
      (node (ref "U8") (pin "1") (pinfunction "KL_1") (pintype "passive"))
      (node (ref "U8") (pin "2") (pinfunction "KL_2") (pintype "passive"))
      (node (ref "U8") (pin "5") (pinfunction "KL_5") (pintype "passive"))
      (node (ref "U8") (pin "6") (pinfunction "KL_6") (pintype "passive"))
      (node (ref "U8") (pin "61") (pinfunction "KL_61") (pintype "passive"))
      (node (ref "U8") (pin "62") (pinfunction "KL_62") (pintype "passive"))
      (node (ref "VGA1") (pin "10") (pinfunction "GND_10") (pintype "passive"))
      (node (ref "VGA1") (pin "5") (pinfunction "GND_5") (pintype "passive"))
    )
    (net (code "104") (name "Net-(C8-Pad-)") (class "Default")
      (node (ref "C8") (pin "-") (pinfunction "-_-") (pintype "passive"))
      (node (ref "JP9") (pin "1") (pinfunction "1_1") (pintype "passive"))
    )
    (net (code "105") (name "Net-(C15-Pad2)") (class "Default")
      (node (ref "C15") (pin "2") (pinfunction "2_2") (pintype "passive"))
      (node (ref "R15") (pin "1") (pinfunction "1_1") (pintype "passive"))
    )
    (net (code "106") (name "Net-(C16-Pad2)") (class "Default")
      (node (ref "C16") (pin "2") (pinfunction "2_2") (pintype "passive"))
      (node (ref "R16") (pin "1") (pinfunction "1_1") (pintype "passive"))
    )
    (net (code "107") (name "Net-(C17-Pad2)") (class "Default")
      (node (ref "C17") (pin "2") (pinfunction "2_2") (pintype "passive"))
      (node (ref "R17") (pin "1") (pinfunction "1_1") (pintype "passive"))
    )
    (net (code "108") (name "Net-(C18-Pad2)") (class "Default")
      (node (ref "C18") (pin "2") (pinfunction "2_2") (pintype "passive"))
      (node (ref "R18") (pin "1") (pinfunction "1_1") (pintype "passive"))
    )
    (net (code "109") (name "Net-(IC1A-VOUTA)") (class "Default")
      (node (ref "IC1") (pin "8") (pinfunction "VOUTA_8") (pintype "output"))
      (node (ref "JP3") (pin "1") (pinfunction "1_1") (pintype "passive"))
    )
    (net (code "110") (name "Net-(IC2A-VOUTA)") (class "Default")
      (node (ref "IC2") (pin "8") (pinfunction "VOUTA_8") (pintype "output"))
      (node (ref "JP4") (pin "1") (pinfunction "1_1") (pintype "passive"))
    )
    (net (code "111") (name "Net-(IC2A-VOUTB)") (class "Default")
      (node (ref "IC2") (pin "6") (pinfunction "VOUTB_6") (pintype "output"))
      (node (ref "JP14") (pin "1") (pinfunction "1_1") (pintype "passive"))
    )
    (net (code "112") (name "Net-(IC3A-VOUTA)") (class "Default")
      (node (ref "IC3") (pin "8") (pinfunction "VOUTA_8") (pintype "output"))
      (node (ref "JP5") (pin "1") (pinfunction "1_1") (pintype "passive"))
    )
    (net (code "113") (name "Net-(JP7-Pad1)") (class "Default")
      (node (ref "JP7") (pin "1") (pinfunction "1_1") (pintype "passive"))
      (node (ref "R13") (pin "2") (pinfunction "2_2") (pintype "passive"))
    )
    (net (code "114") (name "Net-(JP7-Pad2)") (class "Default")
      (node (ref "JP7") (pin "2") (pinfunction "2_2") (pintype "passive"))
      (node (ref "R14") (pin "2") (pinfunction "2_2") (pintype "passive"))
    )
    (net (code "115") (name "Net-(JP8-Pad1)") (class "Default")
      (node (ref "JP8") (pin "1") (pinfunction "1_1") (pintype "passive"))
      (node (ref "R20") (pin "2") (pinfunction "2_2") (pintype "passive"))
    )
    (net (code "116") (name "Net-(JP8-Pad2)") (class "Default")
      (node (ref "JP8") (pin "2") (pinfunction "2_2") (pintype "passive"))
      (node (ref "R21") (pin "2") (pinfunction "2_2") (pintype "passive"))
    )
    (net (code "117") (name "Net-(JP8-Pad3)") (class "Default")
      (node (ref "JP8") (pin "3") (pinfunction "3_3") (pintype "passive"))
      (node (ref "R22") (pin "2") (pinfunction "2_2") (pintype "passive"))
    )
    (net (code "118") (name "Net-(U$1A-+IN)") (class "Default")
      (node (ref "C19") (pin "2") (pinfunction "2_2") (pintype "passive"))
      (node (ref "R26") (pin "2") (pinfunction "2_2") (pintype "passive"))
      (node (ref "R27") (pin "1") (pinfunction "1_1") (pintype "passive"))
      (node (ref "U$1") (pin "3") (pinfunction "+IN_3") (pintype "input"))
      (node (ref "U$1") (pin "5") (pinfunction "+IN_5") (pintype "input"))
    )
    (net (code "119") (name "Net-(U$1A--IN)") (class "Default")
      (node (ref "R15") (pin "2") (pinfunction "2_2") (pintype "passive"))
      (node (ref "R16") (pin "2") (pinfunction "2_2") (pintype "passive"))
      (node (ref "R17") (pin "2") (pinfunction "2_2") (pintype "passive"))
      (node (ref "R18") (pin "2") (pinfunction "2_2") (pintype "passive"))
      (node (ref "R19") (pin "1") (pinfunction "1_1") (pintype "passive"))
      (node (ref "U$1") (pin "2") (pinfunction "-IN_2") (pintype "input"))
    )
    (net (code "120") (name "Net-(U$1A-OUT)") (class "Default")
      (node (ref "R19") (pin "2") (pinfunction "2_2") (pintype "passive"))
      (node (ref "R24") (pin "1") (pinfunction "1_1") (pintype "passive"))
      (node (ref "U$1") (pin "1") (pinfunction "OUT_1") (pintype "output"))
    )
    (net (code "121") (name "Net-(U$1B--IN)") (class "Default")
      (node (ref "C11") (pin "1") (pinfunction "1_1") (pintype "passive"))
      (node (ref "R23") (pin "1") (pinfunction "1_1") (pintype "passive"))
      (node (ref "R24") (pin "2") (pinfunction "2_2") (pintype "passive"))
      (node (ref "U$1") (pin "6") (pinfunction "-IN_6") (pintype "input"))
    )
    (net (code "122") (name "Net-(U$1B-OUT)") (class "Default")
      (node (ref "C8") (pin "+") (pinfunction "+_+") (pintype "passive"))
      (node (ref "R23") (pin "2") (pinfunction "2_2") (pintype "passive"))
      (node (ref "U$1") (pin "7") (pinfunction "OUT_7") (pintype "output"))
    )
    (net (code "123") (name "Net-(U7AC-KL)") (class "Default")
      (node (ref "JP15") (pin "2") (pinfunction "2_2") (pintype "passive"))
      (node (ref "U7") (pin "35") (pinfunction "KL_35") (pintype "passive"))
    )
    (net (code "124") (name "Net-(U7AD-KL)") (class "Default")
      (node (ref "JP15") (pin "3") (pinfunction "3_3") (pintype "passive"))
      (node (ref "U7") (pin "36") (pinfunction "KL_36") (pintype "passive"))
    )
    (net (code "125") (name "Net-(VGA1A-VGA-B)") (class "Default")
      (node (ref "C2") (pin "2") (pinfunction "2_2") (pintype "passive"))
      (node (ref "JP2") (pin "3") (pinfunction "3_3") (pintype "passive"))
      (node (ref "R5") (pin "2") (pinfunction "2_2") (pintype "passive"))
      (node (ref "R6") (pin "2") (pinfunction "2_2") (pintype "passive"))
      (node (ref "R7") (pin "2") (pinfunction "2_2") (pintype "passive"))
      (node (ref "R8") (pin "2") (pinfunction "2_2") (pintype "passive"))
      (node (ref "VGA1") (pin "3") (pinfunction "VGA-B_3") (pintype "bidirectional"))
    )
    (net (code "126") (name "Net-(VGA1A-VGA-G)") (class "Default")
      (node (ref "C1") (pin "2") (pinfunction "2_2") (pintype "passive"))
      (node (ref "JP2") (pin "2") (pinfunction "2_2") (pintype "passive"))
      (node (ref "R1") (pin "2") (pinfunction "2_2") (pintype "passive"))
      (node (ref "R2") (pin "2") (pinfunction "2_2") (pintype "passive"))
      (node (ref "R3") (pin "2") (pinfunction "2_2") (pintype "passive"))
      (node (ref "R4") (pin "2") (pinfunction "2_2") (pintype "passive"))
      (node (ref "VGA1") (pin "2") (pinfunction "VGA-G_2") (pintype "bidirectional"))
    )
    (net (code "127") (name "Net-(VGA1A-VGA-R)") (class "Default")
      (node (ref "C3") (pin "2") (pinfunction "2_2") (pintype "passive"))
      (node (ref "JP2") (pin "1") (pinfunction "1_1") (pintype "passive"))
      (node (ref "R10") (pin "2") (pinfunction "2_2") (pintype "passive"))
      (node (ref "R11") (pin "2") (pinfunction "2_2") (pintype "passive"))
      (node (ref "R12") (pin "2") (pinfunction "2_2") (pintype "passive"))
      (node (ref "R9") (pin "2") (pinfunction "2_2") (pintype "passive"))
      (node (ref "VGA1") (pin "1") (pinfunction "VGA-R_1") (pintype "bidirectional"))
    )
    (net (code "128") (name "unconnected-(IC1A-VOUTB-Pad6)") (class "Default")
      (node (ref "IC1") (pin "6") (pinfunction "VOUTB_6") (pintype "output"))
    )
    (net (code "129") (name "unconnected-(IC3A-VOUTB-Pad6)") (class "Default")
      (node (ref "IC3") (pin "6") (pinfunction "VOUTB_6") (pintype "output"))
    )
    (net (code "130") (name "unconnected-(JP15-Pad1)") (class "Default")
      (node (ref "JP15") (pin "1") (pinfunction "1_1") (pintype "passive"))
    )
    (net (code "131") (name "unconnected-(JP15-Pad4)") (class "Default")
      (node (ref "JP15") (pin "4") (pinfunction "4_4") (pintype "passive"))
    )
    (net (code "132") (name "unconnected-(U7BI-KL-Pad64)") (class "Default")
      (node (ref "U7") (pin "64") (pinfunction "KL_64") (pintype "passive"))
    )
    (net (code "133") (name "unconnected-(U8AI-KL-Pad40)") (class "Default")
      (node (ref "U8") (pin "40") (pinfunction "KL_40") (pintype "passive"))
    )
    (net (code "134") (name "unconnected-(U8AJ-KL-Pad41)") (class "Default")
      (node (ref "U8") (pin "41") (pinfunction "KL_41") (pintype "passive"))
    )
    (net (code "135") (name "unconnected-(U8AK-KL-Pad42)") (class "Default")
      (node (ref "U8") (pin "42") (pinfunction "KL_42") (pintype "passive"))
    )
    (net (code "136") (name "unconnected-(U8AL-KL-Pad43)") (class "Default")
      (node (ref "U8") (pin "43") (pinfunction "KL_43") (pintype "passive"))
    )
    (net (code "137") (name "unconnected-(U8AM-KL-Pad44)") (class "Default")
      (node (ref "U8") (pin "44") (pinfunction "KL_44") (pintype "passive"))
    )
    (net (code "138") (name "unconnected-(U8AN-KL-Pad45)") (class "Default")
      (node (ref "U8") (pin "45") (pinfunction "KL_45") (pintype "passive"))
    )
    (net (code "139") (name "unconnected-(U8AO-KL-Pad46)") (class "Default")
      (node (ref "U8") (pin "46") (pinfunction "KL_46") (pintype "passive"))
    )
    (net (code "140") (name "unconnected-(U8AX-KL-Pad54)") (class "Default")
      (node (ref "U8") (pin "54") (pinfunction "KL_54") (pintype "passive"))
    )
    (net (code "141") (name "unconnected-(U8BI-KL-Pad64)") (class "Default")
      (node (ref "U8") (pin "64") (pinfunction "KL_64") (pintype "passive"))
    )
    (net (code "142") (name "unconnected-(U8F-KL-Pad14)") (class "Default")
      (node (ref "U8") (pin "14") (pinfunction "KL_14") (pintype "passive"))
    )
    (net (code "143") (name "unconnected-(VGA1A-ID0{slash}RES-Pad11)") (class "Default")
      (node (ref "VGA1") (pin "11") (pinfunction "ID0/RES_11") (pintype "passive"))
    )
    (net (code "144") (name "unconnected-(VGA1A-ID1{slash}SDA-Pad12)") (class "Default")
      (node (ref "VGA1") (pin "12") (pinfunction "ID1/SDA_12") (pintype "bidirectional"))
    )
    (net (code "145") (name "unconnected-(VGA1A-ID2{slash}RES-Pad4)") (class "Default")
      (node (ref "VGA1") (pin "4") (pinfunction "ID2/RES_4") (pintype "passive"))
    )
    (net (code "146") (name "unconnected-(VGA1A-ID3{slash}SCL-Pad15)") (class "Default")
      (node (ref "VGA1") (pin "15") (pinfunction "ID3/SCL_15") (pintype "bidirectional"))
    )
    (net (code "147") (name "unconnected-(VGA1A-VGA-B--Pad8)") (class "Default")
      (node (ref "VGA1") (pin "8") (pinfunction "VGA-B-_8") (pintype "passive"))
    )
    (net (code "148") (name "unconnected-(VGA1A-VGA-G--Pad7)") (class "Default")
      (node (ref "VGA1") (pin "7") (pinfunction "VGA-G-_7") (pintype "passive"))
    )
    (net (code "149") (name "unconnected-(VGA1A-VGA-R--Pad6)") (class "Default")
      (node (ref "VGA1") (pin "6") (pinfunction "VGA-R-_6") (pintype "passive"))
    )
  )
)
